# chicker.net
KiCad netlist of a schematic drawn in Altium Designer
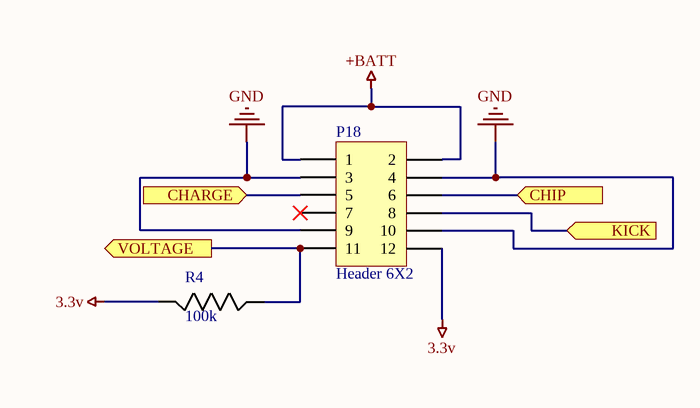
[diagram p0: chicker.SchDoc]

(export (version "E")
  (design (tool "Eeschema 10.0.6"))
  (components
    (comp (ref "P18")
      (value "Header 6X2")
      (footprint "HDR2X6")
      (description "Header, 6-Pin, Dual row")
      (fields (field (name "PUBLISHER") "Altium Limited"))
      (libsource (lib "Miscellaneous Connectors") (part "Header 6X2"))
    )
    (comp (ref "R4")
      (value "100k")
      (footprint "RESC2012X60")
      (description "RES SMD 100k OHM 1% 1/8W 0805")
      (fields (field (name "MP") "RC0805FR-07100RL") (field (name "MF") "Yageo"))
      (libsource (lib "RC0805FR-07100RL") (part "RC0805FR-07100RL"))
    )
  )
  (nets
    (net (code "1") (name "+BATT") (class "Default")
      (node (ref "P18") (pin "1") (pinfunction "1_1") (pintype "passive"))
      (node (ref "P18") (pin "2") (pinfunction "2_2") (pintype "passive"))
    )
    (net (code "2") (name "/CHARGE") (class "Default")
      (node (ref "P18") (pin "5") (pinfunction "5_5") (pintype "passive"))
    )
    (net (code "3") (name "/CHIP") (class "Default")
      (node (ref "P18") (pin "6") (pinfunction "6_6") (pintype "passive"))
    )
    (net (code "4") (name "/KICK") (class "Default")
      (node (ref "P18") (pin "8") (pinfunction "8_8") (pintype "passive"))
    )
    (net (code "5") (name "/VOLTAGE") (class "Default")
      (node (ref "P18") (pin "11") (pinfunction "11_11") (pintype "passive"))
      (node (ref "R4") (pin "2") (pinfunction "2_2") (pintype "passive"))
    )
    (net (code "6") (name "3.3v") (class "Default")
      (node (ref "P18") (pin "12") (pinfunction "12_12") (pintype "passive"))
      (node (ref "R4") (pin "1") (pinfunction "1_1") (pintype "passive"))
    )
    (net (code "7") (name "GND") (class "Default")
      (node (ref "P18") (pin "10") (pinfunction "10_10") (pintype "passive"))
      (node (ref "P18") (pin "3") (pinfunction "3_3") (pintype "passive"))
      (node (ref "P18") (pin "4") (pinfunction "4_4") (pintype "passive"))
      (node (ref "P18") (pin "9") (pinfunction "9_9") (pintype "passive"))
    )
    (net (code "8") (name "unconnected-(P18-Pad7)") (class "Default")
      (node (ref "P18") (pin "7") (pinfunction "7_7") (pintype "passive+no_connect"))
    )
  )
)
